# USBPD_CH211.net
KiCad netlist of a schematic drawn in Altium Designer
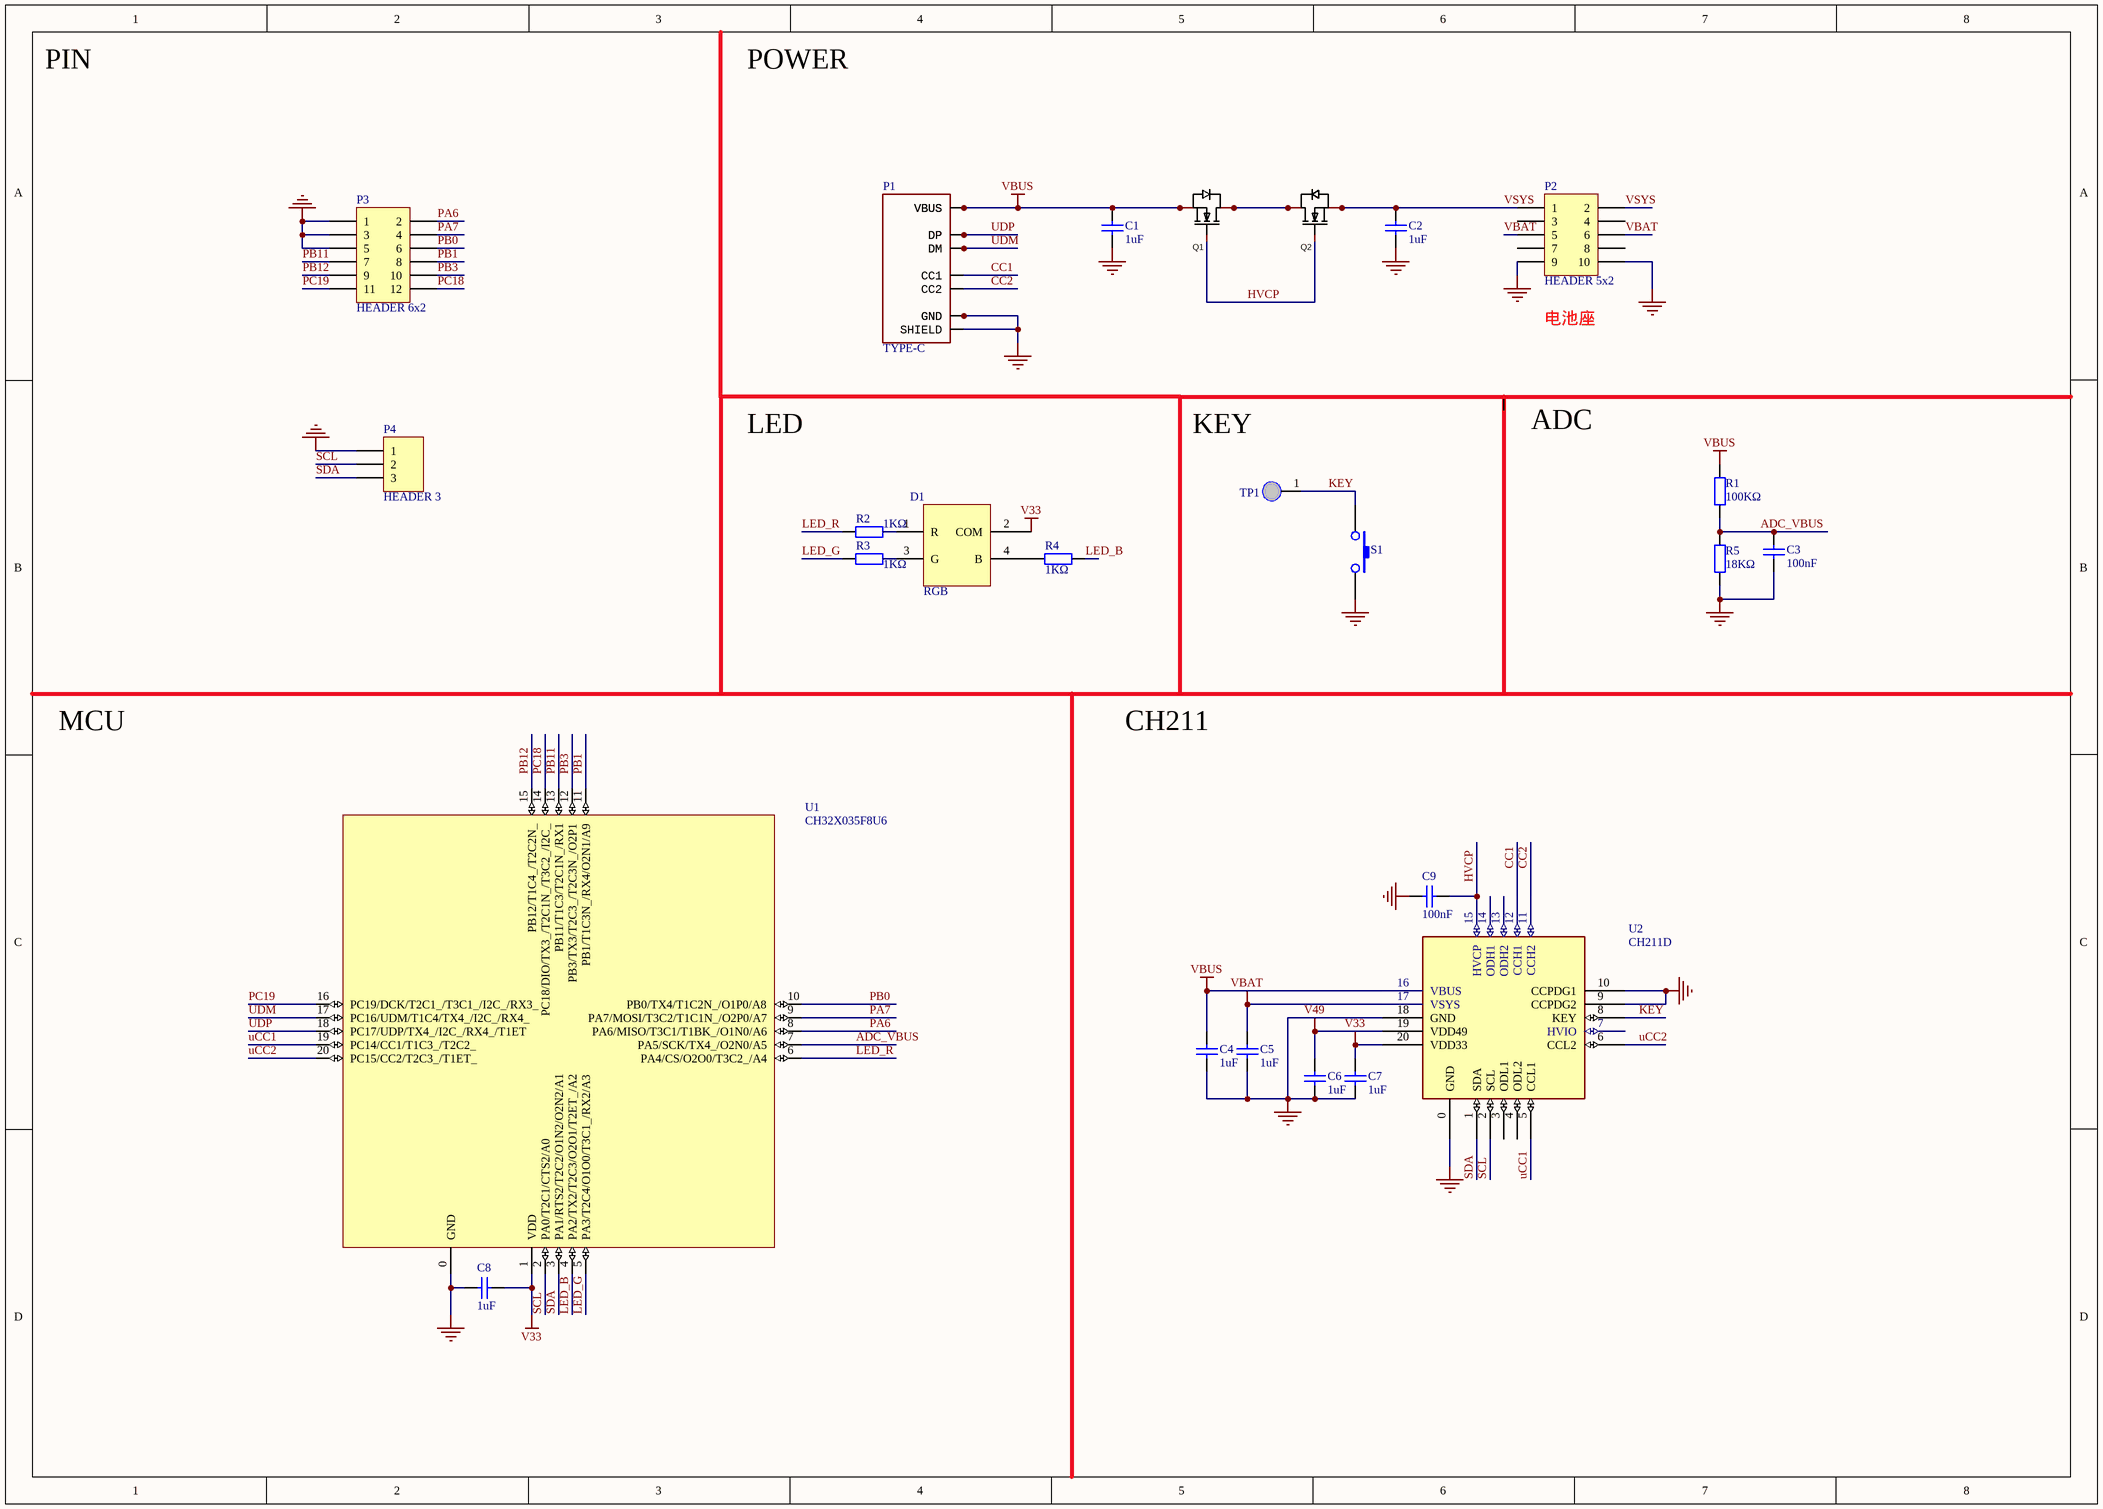
[diagram p0: USBPD_CH211.SchDoc]

(export (version "E")
  (design (tool "Eeschema 10.0.6"))
  (components
    (comp (ref "C1")
      (value "1uF")
      (footprint "0603_C")
      (description "贴片电容")
      (libsource (lib "Miscellaneous Devices LC") (part "0603 100nF (104) 10% 50V"))
    )
    (comp (ref "C2")
      (value "1uF")
      (footprint "0603_C")
      (description "贴片电容")
      (libsource (lib "Miscellaneous Devices LC") (part "0603 100nF (104) 10% 50V"))
    )
    (comp (ref "C3")
      (value "100nF")
      (footprint "0603_C")
      (description "贴片电容")
      (libsource (lib "Miscellaneous Devices LC") (part "0603 100nF (104) 10% 50V"))
    )
    (comp (ref "C4")
      (value "1uF")
      (footprint "0603_C")
      (description "贴片电容")
      (libsource (lib "Miscellaneous Devices LC") (part "0603 100nF (104) 10% 50V"))
    )
    (comp (ref "C5")
      (value "1uF")
      (footprint "0603_C")
      (description "贴片电容")
      (libsource (lib "Miscellaneous Devices LC") (part "0603 100nF (104) 10% 50V"))
    )
    (comp (ref "C6")
      (value "1uF")
      (footprint "0603_C")
      (description "贴片电容")
      (libsource (lib "Miscellaneous Devices LC") (part "0603 100nF (104) 10% 50V"))
    )
    (comp (ref "C7")
      (value "1uF")
      (footprint "0603_C")
      (description "贴片电容")
      (libsource (lib "Miscellaneous Devices LC") (part "0603 100nF (104) 10% 50V"))
    )
    (comp (ref "C8")
      (value "1uF")
      (footprint "0603_C")
      (description "贴片电容")
      (libsource (lib "Miscellaneous Devices LC") (part "0603 1uF (105) 10% 50V"))
    )
    (comp (ref "C9")
      (value "100nF")
      (footprint "0603_C")
      (description "贴片电容")
      (libsource (lib "Miscellaneous Devices LC") (part "0603 100nF (104) 10% 50V"))
    )
    (comp (ref "D1")
      (value "RGB")
      (footprint "RGB 3030")
      (description "共阳")
      (libsource (lib "wch_sch_others") (part "RGB"))
    )
    (comp (ref "P1")
      (value "TYPE-C")
      (footprint "TYPE-C-Receptacle-2.0")
      (libsource (lib "Miscellaneous SCH Lib") (part "TYPE-C-Receptacle-RefDesign"))
    )
    (comp (ref "P2")
      (value "HEADER 5x2")
      (footprint "HDR2X5")
      (description "Header, 5-Pin, Dual row")
      (libsource (lib "wch_sch_others") (part "HEADER 5x2"))
    )
    (comp (ref "P3")
      (value "HEADER 6x2")
      (footprint "HDR2X6")
      (description "Header, 6-Pin, Dual row")
      (libsource (lib "wch_sch_others") (part "HEADER 6x2"))
    )
    (comp (ref "P4")
      (value "HEADER 3")
      (footprint "HDR1X3")
      (description "Header, 3-Pin")
      (libsource (lib "wch_sch_others") (part "HEADER 3"))
    )
    (comp (ref "Q1")
      (value "ASDM40N52E-R")
      (footprint "DFN-8_L3.1-W3.0-P0.65-LS3.3-BL")
      (description "DFN_NMOS")
      (fields (field (name "MANUFACTURER") "Ascend(安森德)"))
      (libsource (lib "Zcc") (part "NMOS_DFN3*3.1"))
    )
    (comp (ref "Q2")
      (value "ASDM40N52E-R")
      (footprint "DFN-8_L3.1-W3.0-P0.65-LS3.3-BL")
      (description "DFN_NMOS")
      (fields (field (name "MANUFACTURER") "Ascend(安森德)"))
      (libsource (lib "Zcc") (part "NMOS_DFN3*3.1"))
    )
    (comp (ref "R1")
      (value "100KΩ")
      (footprint "0603_R")
      (description "贴片电阻")
      (libsource (lib "") (part "0603 100KΩ (1003) 1%_1"))
    )
    (comp (ref "R2")
      (value "1KΩ")
      (footprint "0603_R")
      (description "贴片电阻")
      (libsource (lib "Miscellaneous Devices LC") (part "0603 100KΩ (1003) 1%"))
    )
    (comp (ref "R3")
      (value "1KΩ")
      (footprint "0603_R")
      (description "贴片电阻")
      (libsource (lib "Miscellaneous Devices LC") (part "0603 100KΩ (1003) 1%"))
    )
    (comp (ref "R4")
      (value "1KΩ")
      (footprint "0603_R")
      (description "贴片电阻")
      (libsource (lib "Miscellaneous Devices LC") (part "0603 100KΩ (1003) 1%"))
    )
    (comp (ref "R5")
      (value "18KΩ")
      (footprint "0603_R")
      (description "贴片电阻")
      (libsource (lib "") (part "0603 100KΩ (1003) 1%_1"))
    )
    (comp (ref "S1")
      (value "KEY")
      (footprint "Button DTSZML-6")
      (libsource (lib "wch_sch_others") (part "KEY1"))
    )
    (comp (ref "TP1")
      (value "Testpoint")
      (footprint "TESTPOINT3")
      (description "测试点")
      (libsource (lib "wch_sch_others") (part "Testpoint"))
    )
    (comp (ref "U1")
      (value "CH32X035F8U6")
      (footprint "QFN20_3X3")
      (description "RISC-V MCU with USB/PD/ADC/SPI/I2C/UART/OA")
      (libsource (lib "CHXXX") (part "CH32X035F8U6"))
    )
    (comp (ref "U2")
      (value "CH211D")
      (footprint "QFN20_3X3")
      (description "28V USB PD & Type-C high voltage interface")
      (libsource (lib "CHXXX") (part "CH211D"))
    )
  )
  (nets
    (net (code "1") (name "/ADC_VBUS") (class "Default")
      (node (ref "C3") (pin "2") (pinfunction "2_2") (pintype "passive"))
      (node (ref "R1") (pin "2") (pinfunction "2_2") (pintype "passive"))
      (node (ref "R5") (pin "1") (pinfunction "1_1") (pintype "passive"))
      (node (ref "U1") (pin "7") (pinfunction "PA5/SCK/TX4_/O2N0/A5_7") (pintype "bidirectional"))
    )
    (net (code "2") (name "/CC1") (class "Default")
      (node (ref "P1") (pin "A5") (pinfunction "CC1_A5") (pintype "passive"))
      (node (ref "U2") (pin "12") (pinfunction "CCH1_12") (pintype "bidirectional"))
    )
    (net (code "3") (name "/CC2") (class "Default")
      (node (ref "P1") (pin "B5") (pinfunction "CC2_B5") (pintype "passive"))
      (node (ref "U2") (pin "11") (pinfunction "CCH2_11") (pintype "bidirectional"))
    )
    (net (code "4") (name "/HVCP") (class "Default")
      (node (ref "C9") (pin "1") (pinfunction "1_1") (pintype "passive"))
      (node (ref "Q1") (pin "4") (pinfunction "G_4") (pintype "passive"))
      (node (ref "Q2") (pin "4") (pinfunction "G_4") (pintype "passive"))
      (node (ref "U2") (pin "15") (pinfunction "HVCP_15") (pintype "bidirectional"))
    )
    (net (code "5") (name "/KEY") (class "Default")
      (node (ref "S1") (pin "3") (pinfunction "1_3") (pintype "passive"))
      (node (ref "TP1") (pin "1") (pintype "passive"))
      (node (ref "U2") (pin "8") (pinfunction "KEY_8") (pintype "bidirectional"))
    )
    (net (code "6") (name "/LED_B") (class "Default")
      (node (ref "R4") (pin "2") (pinfunction "2_2") (pintype "passive"))
      (node (ref "U1") (pin "4") (pinfunction "PA2/TX2/T2C3/O2O1/T2ET_/A2_4") (pintype "bidirectional"))
    )
    (net (code "7") (name "/LED_G") (class "Default")
      (node (ref "R3") (pin "1") (pinfunction "1_1") (pintype "passive"))
      (node (ref "U1") (pin "5") (pinfunction "PA3/T2C4/O1O0/T3C1_/RX2/A3_5") (pintype "bidirectional"))
    )
    (net (code "8") (name "/LED_R") (class "Default")
      (node (ref "R2") (pin "1") (pinfunction "1_1") (pintype "passive"))
      (node (ref "U1") (pin "6") (pinfunction "PA4/CS/O2O0/T3C2_/A4_6") (pintype "bidirectional"))
    )
    (net (code "9") (name "/PA6") (class "Default")
      (node (ref "P3") (pin "2") (pinfunction "2_2") (pintype "passive"))
      (node (ref "U1") (pin "8") (pinfunction "PA6/MISO/T3C1/T1BK_/O1N0/A6_8") (pintype "bidirectional"))
    )
    (net (code "10") (name "/PA7") (class "Default")
      (node (ref "P3") (pin "4") (pinfunction "4_4") (pintype "passive"))
      (node (ref "U1") (pin "9") (pinfunction "PA7/MOSI/T3C2/T1C1N_/O2P0/A7_9") (pintype "bidirectional"))
    )
    (net (code "11") (name "/PB0") (class "Default")
      (node (ref "P3") (pin "6") (pinfunction "6_6") (pintype "passive"))
      (node (ref "U1") (pin "10") (pinfunction "PB0/TX4/T1C2N_/O1P0/A8_10") (pintype "bidirectional"))
    )
    (net (code "12") (name "/PB1") (class "Default")
      (node (ref "P3") (pin "8") (pinfunction "8_8") (pintype "passive"))
      (node (ref "U1") (pin "11") (pinfunction "PB1/T1C3N_/RX4/O2N1/A9_11") (pintype "bidirectional"))
    )
    (net (code "13") (name "/PB3") (class "Default")
      (node (ref "P3") (pin "10") (pinfunction "10_10") (pintype "passive"))
      (node (ref "U1") (pin "12") (pinfunction "PB3/TX3/T2C3_/T2C3N_/O2P1_12") (pintype "bidirectional"))
    )
    (net (code "14") (name "/PB11") (class "Default")
      (node (ref "P3") (pin "7") (pinfunction "7_7") (pintype "passive"))
      (node (ref "U1") (pin "13") (pinfunction "PB11/T1C3/T2C1N_/RX1_13") (pintype "bidirectional"))
    )
    (net (code "15") (name "/PB12") (class "Default")
      (node (ref "P3") (pin "9") (pinfunction "9_9") (pintype "passive"))
      (node (ref "U1") (pin "15") (pinfunction "PB12/T1C4_/T2C2N__15") (pintype "bidirectional"))
    )
    (net (code "16") (name "/PC18") (class "Default")
      (node (ref "P3") (pin "12") (pinfunction "12_12") (pintype "passive"))
      (node (ref "U1") (pin "14") (pinfunction "PC18/DIO/TX3_/T2C1N_/T3C2_/I2C__14") (pintype "bidirectional"))
    )
    (net (code "17") (name "/PC19") (class "Default")
      (node (ref "P3") (pin "11") (pinfunction "11_11") (pintype "passive"))
      (node (ref "U1") (pin "16") (pinfunction "PC19/DCK/T2C1_/T3C1_/I2C_/RX3__16") (pintype "bidirectional"))
    )
    (net (code "18") (name "/SCL") (class "Default")
      (node (ref "P4") (pin "2") (pinfunction "2_2") (pintype "passive"))
      (node (ref "U1") (pin "2") (pinfunction "PA0/T2C1/CTS2/A0_2") (pintype "bidirectional"))
      (node (ref "U2") (pin "2") (pinfunction "SCL_2") (pintype "bidirectional"))
    )
    (net (code "19") (name "/SDA") (class "Default")
      (node (ref "P4") (pin "3") (pinfunction "3_3") (pintype "passive"))
      (node (ref "U1") (pin "3") (pinfunction "PA1/RTS2/T2C2/O1N2/O2N2/A1_3") (pintype "bidirectional"))
      (node (ref "U2") (pin "1") (pinfunction "SDA_1") (pintype "bidirectional"))
    )
    (net (code "20") (name "/UDM") (class "Default")
      (node (ref "P1") (pin "A7") (pinfunction "DM_A7") (pintype "passive"))
      (node (ref "P1") (pin "B7") (pinfunction "DM_B7") (pintype "passive"))
      (node (ref "U1") (pin "17") (pinfunction "PC16/UDM/T1C4/TX4_/I2C_/RX4__17") (pintype "bidirectional"))
    )
    (net (code "21") (name "/UDP") (class "Default")
      (node (ref "P1") (pin "A6") (pinfunction "DP_A6") (pintype "passive"))
      (node (ref "P1") (pin "B6") (pinfunction "DP_B6") (pintype "passive"))
      (node (ref "U1") (pin "18") (pinfunction "PC17/UDP/TX4_/I2C_/RX4_/T1ET_18") (pintype "bidirectional"))
    )
    (net (code "22") (name "/VSYS") (class "Default")
      (node (ref "C2") (pin "2") (pinfunction "2_2") (pintype "passive"))
      (node (ref "P2") (pin "1") (pinfunction "1_1") (pintype "passive"))
      (node (ref "P2") (pin "2") (pinfunction "2_2") (pintype "passive"))
      (node (ref "Q2") (pin "1") (pinfunction "S_1") (pintype "passive"))
      (node (ref "Q2") (pin "2") (pinfunction "S_2") (pintype "passive"))
      (node (ref "Q2") (pin "3") (pinfunction "S_3") (pintype "passive"))
    )
    (net (code "23") (name "/uCC1") (class "Default")
      (node (ref "U1") (pin "19") (pinfunction "PC14/CC1/T1C3_/T2C2__19") (pintype "bidirectional"))
      (node (ref "U2") (pin "5") (pinfunction "CCL1_5") (pintype "bidirectional"))
    )
    (net (code "24") (name "/uCC2") (class "Default")
      (node (ref "U1") (pin "20") (pinfunction "PC15/CC2/T2C3_/T1ET__20") (pintype "bidirectional"))
      (node (ref "U2") (pin "6") (pinfunction "CCL2_6") (pintype "bidirectional"))
    )
    (net (code "25") (name "GND") (class "Default")
      (node (ref "C1") (pin "1") (pinfunction "1_1") (pintype "passive"))
      (node (ref "C2") (pin "1") (pinfunction "1_1") (pintype "passive"))
      (node (ref "C3") (pin "1") (pinfunction "1_1") (pintype "passive"))
      (node (ref "C4") (pin "1") (pinfunction "1_1") (pintype "passive"))
      (node (ref "C5") (pin "1") (pinfunction "1_1") (pintype "passive"))
      (node (ref "C6") (pin "1") (pinfunction "1_1") (pintype "passive"))
      (node (ref "C7") (pin "1") (pinfunction "1_1") (pintype "passive"))
      (node (ref "C8") (pin "2") (pinfunction "2_2") (pintype "passive"))
      (node (ref "C9") (pin "2") (pinfunction "2_2") (pintype "passive"))
      (node (ref "P1") (pin "0") (pinfunction "SHIELD_0") (pintype "passive"))
      (node (ref "P1") (pin "A1") (pinfunction "GND_A1") (pintype "passive"))
      (node (ref "P1") (pin "A12") (pinfunction "GND_A12") (pintype "passive"))
      (node (ref "P1") (pin "B1") (pinfunction "GND_B1") (pintype "passive"))
      (node (ref "P1") (pin "B12") (pinfunction "GND_B12") (pintype "passive"))
      (node (ref "P2") (pin "10") (pinfunction "10_10") (pintype "passive"))
      (node (ref "P2") (pin "9") (pinfunction "9_9") (pintype "passive"))
      (node (ref "P3") (pin "1") (pinfunction "1_1") (pintype "passive"))
      (node (ref "P3") (pin "3") (pinfunction "3_3") (pintype "passive"))
      (node (ref "P3") (pin "5") (pinfunction "5_5") (pintype "passive"))
      (node (ref "P4") (pin "1") (pinfunction "1_1") (pintype "passive"))
      (node (ref "R5") (pin "2") (pinfunction "2_2") (pintype "passive"))
      (node (ref "S1") (pin "2") (pinfunction "2_2") (pintype "passive"))
      (node (ref "U1") (pin "0") (pinfunction "GND_0") (pintype "power_in"))
      (node (ref "U2") (pin "0") (pinfunction "GND_0") (pintype "power_in"))
      (node (ref "U2") (pin "10") (pinfunction "CCPDG1_10") (pintype "power_in"))
      (node (ref "U2") (pin "18") (pinfunction "GND_18") (pintype "power_in"))
      (node (ref "U2") (pin "9") (pinfunction "CCPDG2_9") (pintype "power_in"))
    )
    (net (code "26") (name "Net-(D1-B)") (class "Default")
      (node (ref "D1") (pin "4") (pinfunction "B_4") (pintype "passive"))
      (node (ref "R4") (pin "1") (pinfunction "1_1") (pintype "passive"))
    )
    (net (code "27") (name "Net-(D1-G)") (class "Default")
      (node (ref "D1") (pin "3") (pinfunction "G_3") (pintype "passive"))
      (node (ref "R3") (pin "2") (pinfunction "2_2") (pintype "passive"))
    )
    (net (code "28") (name "Net-(D1-R)") (class "Default")
      (node (ref "D1") (pin "1") (pinfunction "R_1") (pintype "passive"))
      (node (ref "R2") (pin "2") (pinfunction "2_2") (pintype "passive"))
    )
    (net (code "29") (name "Net-(Q1-D-Pad5)") (class "Default")
      (node (ref "Q1") (pin "5") (pinfunction "D_5") (pintype "passive"))
      (node (ref "Q1") (pin "6") (pinfunction "D_6") (pintype "passive"))
      (node (ref "Q1") (pin "7") (pinfunction "D_7") (pintype "passive"))
      (node (ref "Q1") (pin "8") (pinfunction "D_8") (pintype "passive"))
      (node (ref "Q2") (pin "5") (pinfunction "D_5") (pintype "passive"))
      (node (ref "Q2") (pin "6") (pinfunction "D_6") (pintype "passive"))
      (node (ref "Q2") (pin "7") (pinfunction "D_7") (pintype "passive"))
      (node (ref "Q2") (pin "8") (pinfunction "D_8") (pintype "passive"))
    )
    (net (code "30") (name "V33") (class "Default")
      (node (ref "C7") (pin "2") (pinfunction "2_2") (pintype "passive"))
      (node (ref "C8") (pin "1") (pinfunction "1_1") (pintype "passive"))
      (node (ref "D1") (pin "2") (pinfunction "COM_2") (pintype "passive"))
      (node (ref "U1") (pin "1") (pinfunction "VDD_1") (pintype "power_in"))
      (node (ref "U2") (pin "20") (pinfunction "VDD33_20") (pintype "power_in"))
    )
    (net (code "31") (name "V49") (class "Default")
      (node (ref "C6") (pin "2") (pinfunction "2_2") (pintype "passive"))
      (node (ref "U2") (pin "19") (pinfunction "VDD49_19") (pintype "power_in"))
    )
    (net (code "32") (name "VBAT") (class "Default")
      (node (ref "C5") (pin "2") (pinfunction "2_2") (pintype "passive"))
      (node (ref "P2") (pin "5") (pinfunction "5_5") (pintype "passive"))
      (node (ref "P2") (pin "6") (pinfunction "6_6") (pintype "passive"))
      (node (ref "U2") (pin "17") (pinfunction "VSYS_17") (pintype "power_in"))
    )
    (net (code "33") (name "VBUS") (class "Default")
      (node (ref "C1") (pin "2") (pinfunction "2_2") (pintype "passive"))
      (node (ref "C4") (pin "2") (pinfunction "2_2") (pintype "passive"))
      (node (ref "P1") (pin "A4") (pinfunction "VBUS_A4") (pintype "passive"))
      (node (ref "P1") (pin "A9") (pinfunction "VBUS_A9") (pintype "passive"))
      (node (ref "P1") (pin "B4") (pinfunction "VBUS_B4") (pintype "passive"))
      (node (ref "P1") (pin "B9") (pinfunction "VBUS_B9") (pintype "passive"))
      (node (ref "Q1") (pin "1") (pinfunction "S_1") (pintype "passive"))
      (node (ref "Q1") (pin "2") (pinfunction "S_2") (pintype "passive"))
      (node (ref "Q1") (pin "3") (pinfunction "S_3") (pintype "passive"))
      (node (ref "R1") (pin "1") (pinfunction "1_1") (pintype "passive"))
      (node (ref "U2") (pin "16") (pinfunction "VBUS_16") (pintype "power_in"))
    )
    (net (code "34") (name "unconnected-(P2-Pad3)") (class "Default")
      (node (ref "P2") (pin "3") (pinfunction "3_3") (pintype "passive"))
    )
    (net (code "35") (name "unconnected-(P2-Pad4)") (class "Default")
      (node (ref "P2") (pin "4") (pinfunction "4_4") (pintype "passive"))
    )
    (net (code "36") (name "unconnected-(P2-Pad7)") (class "Default")
      (node (ref "P2") (pin "7") (pinfunction "7_7") (pintype "passive"))
    )
    (net (code "37") (name "unconnected-(P2-Pad8)") (class "Default")
      (node (ref "P2") (pin "8") (pinfunction "8_8") (pintype "passive"))
    )
    (net (code "38") (name "unconnected-(U2-HVIO-Pad7)") (class "Default")
      (node (ref "U2") (pin "7") (pinfunction "HVIO_7") (pintype "bidirectional"))
    )
    (net (code "39") (name "unconnected-(U2-ODH1-Pad14)") (class "Default")
      (node (ref "U2") (pin "14") (pinfunction "ODH1_14") (pintype "bidirectional"))
    )
    (net (code "40") (name "unconnected-(U2-ODH2-Pad13)") (class "Default")
      (node (ref "U2") (pin "13") (pinfunction "ODH2_13") (pintype "bidirectional"))
    )
    (net (code "41") (name "unconnected-(U2-ODL1-Pad3)") (class "Default")
      (node (ref "U2") (pin "3") (pinfunction "ODL1_3") (pintype "bidirectional"))
    )
    (net (code "42") (name "unconnected-(U2-ODL2-Pad4)") (class "Default")
      (node (ref "U2") (pin "4") (pinfunction "ODL2_4") (pintype "bidirectional"))
    )
  )
)
